# USB3_Replication.net
KiCad netlist of a schematic drawn in Altium Designer
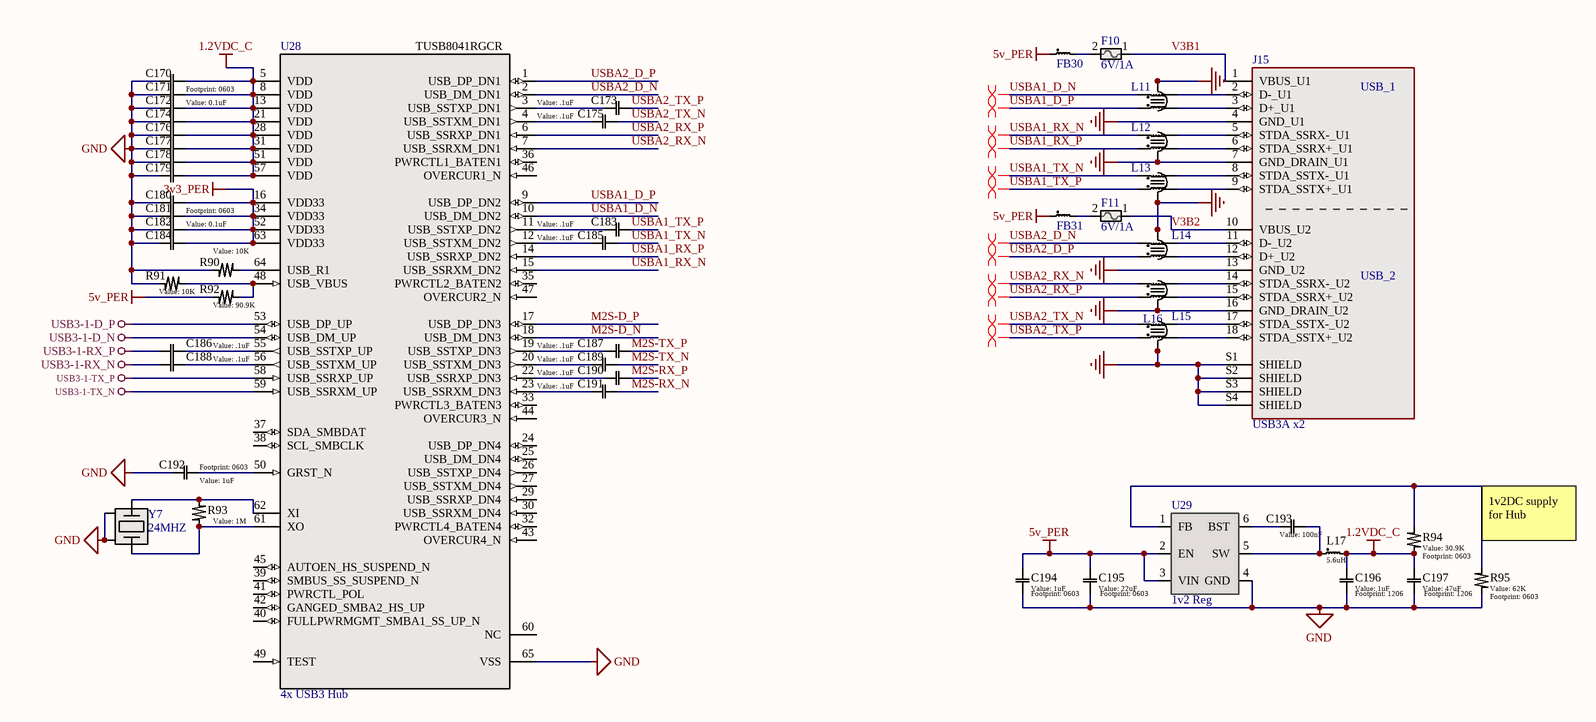
[diagram p0: USB3_Replication.SchDoc]

(export (version "E")
  (design (tool "Eeschema 10.0.6"))
  (components
    (comp (ref "C170")
      (value "0.1uF")
      (footprint "0603")
      (fields
        (field (name "VOLTAGE") "10V")
        (field (name "TOLERANCE") "10%")
        (field (name "Comment") "Generic Capacitor")
      )
      (libsource (lib "Capacitors") (part "Generic Capacitor"))
    )
    (comp (ref "C171")
      (value "Generic Capacitor")
      (footprint "0603")
      (fields (field (name "VOLTAGE") "10V") (field (name "TOLERANCE") "10%"))
      (libsource (lib "Capacitors") (part "Generic Capacitor"))
    )
    (comp (ref "C172")
      (value "Generic Capacitor")
      (footprint "0603")
      (fields (field (name "VOLTAGE") "10V") (field (name "TOLERANCE") "10%"))
      (libsource (lib "Capacitors") (part "Generic Capacitor"))
    )
    (comp (ref "C173")
      (value ".1uF")
      (footprint "0603")
      (fields
        (field (name "VOLTAGE") ">10V")
        (field (name "TOLERANCE") "10%")
        (field (name "Comment") "Generic Capacitor")
      )
      (libsource (lib "Capacitors") (part "Generic Capacitor"))
    )
    (comp (ref "C174")
      (value "Generic Capacitor")
      (footprint "0603")
      (fields (field (name "VOLTAGE") "10V") (field (name "TOLERANCE") "10%"))
      (libsource (lib "Capacitors") (part "Generic Capacitor"))
    )
    (comp (ref "C175")
      (value ".1uF")
      (footprint "0603")
      (fields
        (field (name "VOLTAGE") ">10V")
        (field (name "TOLERANCE") "10%")
        (field (name "Comment") "Generic Capacitor")
      )
      (libsource (lib "Capacitors") (part "Generic Capacitor"))
    )
    (comp (ref "C176")
      (value "Generic Capacitor")
      (footprint "0603")
      (fields (field (name "VOLTAGE") "10V") (field (name "TOLERANCE") "10%"))
      (libsource (lib "Capacitors") (part "Generic Capacitor"))
    )
    (comp (ref "C177")
      (value "Generic Capacitor")
      (footprint "0603")
      (fields (field (name "VOLTAGE") "10V") (field (name "TOLERANCE") "10%"))
      (libsource (lib "Capacitors") (part "Generic Capacitor"))
    )
    (comp (ref "C178")
      (value "Generic Capacitor")
      (footprint "0603")
      (fields (field (name "VOLTAGE") "10V") (field (name "TOLERANCE") "10%"))
      (libsource (lib "Capacitors") (part "Generic Capacitor"))
    )
    (comp (ref "C179")
      (value "Generic Capacitor")
      (footprint "0603")
      (fields (field (name "VOLTAGE") "10V") (field (name "TOLERANCE") "10%"))
      (libsource (lib "Capacitors") (part "Generic Capacitor"))
    )
    (comp (ref "C180")
      (value "0.1uF")
      (footprint "0603")
      (fields
        (field (name "VOLTAGE") "10V")
        (field (name "TOLERANCE") "10%")
        (field (name "Comment") "Generic Capacitor")
      )
      (libsource (lib "Capacitors") (part "Generic Capacitor"))
    )
    (comp (ref "C181")
      (value "Generic Capacitor")
      (footprint "0603")
      (fields (field (name "VOLTAGE") "10V") (field (name "TOLERANCE") "10%"))
      (libsource (lib "Capacitors") (part "Generic Capacitor"))
    )
    (comp (ref "C182")
      (value "Generic Capacitor")
      (footprint "0603")
      (fields (field (name "VOLTAGE") "10V") (field (name "TOLERANCE") "10%"))
      (libsource (lib "Capacitors") (part "Generic Capacitor"))
    )
    (comp (ref "C183")
      (value ".1uF")
      (footprint "0603")
      (fields
        (field (name "VOLTAGE") ">10V")
        (field (name "TOLERANCE") "10%")
        (field (name "Comment") "Generic Capacitor")
      )
      (libsource (lib "Capacitors") (part "Generic Capacitor"))
    )
    (comp (ref "C184")
      (value "Generic Capacitor")
      (footprint "0603")
      (fields (field (name "VOLTAGE") "10V") (field (name "TOLERANCE") "10%"))
      (libsource (lib "Capacitors") (part "Generic Capacitor"))
    )
    (comp (ref "C185")
      (value ".1uF")
      (footprint "0603")
      (fields
        (field (name "VOLTAGE") ">10V")
        (field (name "TOLERANCE") "10%")
        (field (name "Comment") "Generic Capacitor")
      )
      (libsource (lib "Capacitors") (part "Generic Capacitor"))
    )
    (comp (ref "C186")
      (value ".1uF")
      (footprint "0603")
      (fields
        (field (name "VOLTAGE") ">10V")
        (field (name "TOLERANCE") "10%")
        (field (name "Comment") "Generic Capacitor")
      )
      (libsource (lib "Capacitors") (part "Generic Capacitor"))
    )
    (comp (ref "C187")
      (value ".1uF")
      (footprint "0603")
      (fields
        (field (name "VOLTAGE") ">10V")
        (field (name "TOLERANCE") "10%")
        (field (name "Comment") "Generic Capacitor")
      )
      (libsource (lib "Capacitors") (part "Generic Capacitor"))
    )
    (comp (ref "C188")
      (value ".1uF")
      (footprint "0603")
      (fields
        (field (name "VOLTAGE") ">10V")
        (field (name "TOLERANCE") "10%")
        (field (name "Comment") "Generic Capacitor")
      )
      (libsource (lib "Capacitors") (part "Generic Capacitor"))
    )
    (comp (ref "C189")
      (value ".1uF")
      (footprint "0603")
      (fields
        (field (name "VOLTAGE") ">10V")
        (field (name "TOLERANCE") "10%")
        (field (name "Comment") "Generic Capacitor")
      )
      (libsource (lib "Capacitors") (part "Generic Capacitor"))
    )
    (comp (ref "C190")
      (value ".1uF")
      (footprint "0603")
      (fields
        (field (name "VOLTAGE") ">10V")
        (field (name "TOLERANCE") "10%")
        (field (name "Comment") "Generic Capacitor")
      )
      (libsource (lib "Capacitors") (part "Generic Capacitor"))
    )
    (comp (ref "C191")
      (value ".1uF")
      (footprint "0603")
      (fields
        (field (name "VOLTAGE") ">10V")
        (field (name "TOLERANCE") "10%")
        (field (name "Comment") "Generic Capacitor")
      )
      (libsource (lib "Capacitors") (part "Generic Capacitor"))
    )
    (comp (ref "C192")
      (value "1uF")
      (footprint "0603")
      (fields
        (field (name "VOLTAGE") ">10V")
        (field (name "TOLERANCE") "10%")
        (field (name "Comment") "Generic Capacitor")
      )
      (libsource (lib "Capacitors") (part "Generic Capacitor"))
    )
    (comp (ref "C193")
      (value "100nF")
      (footprint "0603")
      (fields
        (field (name "VOLTAGE") ">10V")
        (field (name "TOLERANCE") "10%")
        (field (name "Comment") "Generic Capacitor")
      )
      (libsource (lib "Capacitors") (part "Generic Capacitor"))
    )
    (comp (ref "C194")
      (value "1uF")
      (footprint "0603")
      (fields
        (field (name "VOLTAGE") ">10V")
        (field (name "TOLERANCE") "10%")
        (field (name "Comment") "Generic Capacitor")
      )
      (libsource (lib "Capacitors") (part "Generic Capacitor"))
    )
    (comp (ref "C195")
      (value "22uF")
      (footprint "0603")
      (fields
        (field (name "VOLTAGE") ">10V")
        (field (name "TOLERANCE") "10%")
        (field (name "Comment") "Generic Capacitor")
      )
      (libsource (lib "Capacitors") (part "Generic Capacitor"))
    )
    (comp (ref "C196")
      (value "1uF")
      (footprint "1206")
      (fields
        (field (name "VOLTAGE") ">10V")
        (field (name "TOLERANCE") "10%")
        (field (name "Comment") "Generic Capacitor")
      )
      (libsource (lib "Capacitors") (part "Generic Capacitor"))
    )
    (comp (ref "C197")
      (value "47uF")
      (footprint "1206")
      (fields
        (field (name "VOLTAGE") ">10V")
        (field (name "TOLERANCE") "10%")
        (field (name "Comment") "Generic Capacitor")
      )
      (libsource (lib "Capacitors") (part "Generic Capacitor"))
    )
    (comp (ref "F10")
      (value "6V/1A")
      (footprint "0805")
      (description "Polymeric PTC Resettable Fuse 6V 1 A Ih Surface Mount 0805 (2012 Metric), Concave")
      (fields (field (name "MANUFACTURER") "Bel") (field (name "MANUFACTURER PART NUMBER") "0ZCK0100FF2E"))
      (libsource (lib "Regulators") (part "0ZCK0100FF2E"))
    )
    (comp (ref "F11")
      (value "6V/1A")
      (footprint "0805")
      (description "Polymeric PTC Resettable Fuse 6V 1 A Ih Surface Mount 0805 (2012 Metric), Concave")
      (fields (field (name "MANUFACTURER") "Bel") (field (name "MANUFACTURER PART NUMBER") "0ZCK0100FF2E"))
      (libsource (lib "Regulators") (part "0ZCK0100FF2E"))
    )
    (comp (ref "FB30")
      (value "0603 Ferrite")
      (footprint "0603")
      (description "120 Ohms @ 100 MHz 1 Signal Line Ferrite Bead 0603 (1608 Metric) 500mA 180mOhm")
      (fields
        (field (name "MANUFACTURER") "Pulse")
        (field (name "MANUFACTURER PART NUMBER") "PE-0603FB121ST")
      )
      (libsource (lib "Inductors") (part "PE-0603FB121ST"))
    )
    (comp (ref "FB31")
      (value "0603 Ferrite")
      (footprint "0603")
      (description "120 Ohms @ 100 MHz 1 Signal Line Ferrite Bead 0603 (1608 Metric) 500mA 180mOhm")
      (fields
        (field (name "MANUFACTURER") "Pulse")
        (field (name "MANUFACTURER PART NUMBER") "PE-0603FB121ST")
      )
      (libsource (lib "Inductors") (part "PE-0603FB121ST"))
    )
    (comp (ref "J15")
      (value "USB3A x2")
      (footprint "0484060003")
      (fields (field (name "MP") "0484060003") (field (name "MF") "Molex"))
      (libsource (lib "Connectors") (part "0484060003"))
    )
    (comp (ref "L11")
      (value "2CH CMC")
      (footprint "SMD-6-2CH")
      (description "35Ω@100MHz -40℃~+85℃ 4Ω 5V 2 100mA SMD Common Mode Filters ROHS")
      (libsource (lib "") (part "ICMEF112P350MFR_1"))
    )
    (comp (ref "L12")
      (value "2CH CMC")
      (footprint "SMD-6-2CH")
      (description "35Ω@100MHz -40℃~+85℃ 4Ω 5V 2 100mA SMD Common Mode Filters ROHS")
      (libsource (lib "Inductors") (part "ICMEF112P350MFR"))
    )
    (comp (ref "L13")
      (value "2CH CMC")
      (footprint "SMD-6-2CH")
      (description "35Ω@100MHz -40℃~+85℃ 4Ω 5V 2 100mA SMD Common Mode Filters ROHS")
      (libsource (lib "Inductors") (part "ICMEF112P350MFR"))
    )
    (comp (ref "L14")
      (value "2CH CMC")
      (footprint "SMD-6-2CH")
      (description "35Ω@100MHz -40℃~+85℃ 4Ω 5V 2 100mA SMD Common Mode Filters ROHS")
      (libsource (lib "") (part "ICMEF112P350MFR_1"))
    )
    (comp (ref "L15")
      (value "2CH CMC")
      (footprint "SMD-6-2CH")
      (description "35Ω@100MHz -40℃~+85℃ 4Ω 5V 2 100mA SMD Common Mode Filters ROHS")
      (libsource (lib "Inductors") (part "ICMEF112P350MFR"))
    )
    (comp (ref "L16")
      (value "2CH CMC")
      (footprint "SMD-6-2CH")
      (description "35Ω@100MHz -40℃~+85℃ 4Ω 5V 2 100mA SMD Common Mode Filters ROHS")
      (libsource (lib "Inductors") (part "ICMEF112P350MFR"))
    )
    (comp (ref "L17")
      (value "5.6uH")
      (footprint "TMPC0402HP")
      (description "2A 5.6uH ±20% SMD Power Inductor")
      (libsource (lib "Inductors") (part "TMPC0402HP-5R6MG-Z02"))
    )
    (comp (ref "R90")
      (value "10K")
      (footprint "0603")
      (fields
        (field (name "TOLERANCE") "1%")
        (field (name "POWER") "1/10W")
        (field (name "Comment") "Generic Resistor")
      )
      (libsource (lib "Resistors") (part "Generic Resistor"))
    )
    (comp (ref "R91")
      (value "10K")
      (footprint "0603")
      (fields
        (field (name "TOLERANCE") "1%")
        (field (name "POWER") "1/10W")
        (field (name "Comment") "Generic Resistor")
      )
      (libsource (lib "Resistors") (part "Generic Resistor"))
    )
    (comp (ref "R92")
      (value "90.9K")
      (footprint "0603")
      (fields
        (field (name "TOLERANCE") "1%")
        (field (name "POWER") "1/10W")
        (field (name "Comment") "Generic Resistor")
      )
      (libsource (lib "Resistors") (part "Generic Resistor"))
    )
    (comp (ref "R93")
      (value "1M")
      (footprint "0603")
      (fields
        (field (name "TOLERANCE") "1%")
        (field (name "POWER") "1/10W")
        (field (name "Comment") "Generic Resistor")
      )
      (libsource (lib "Resistors") (part "Generic Resistor"))
    )
    (comp (ref "R94")
      (value "30.9K")
      (footprint "0603")
      (fields
        (field (name "TOLERANCE") "1%")
        (field (name "POWER") "1/10W")
        (field (name "Comment") "Generic Resistor")
      )
      (libsource (lib "Resistors") (part "Generic Resistor"))
    )
    (comp (ref "R95")
      (value "62K")
      (footprint "0603")
      (fields
        (field (name "TOLERANCE") "1%")
        (field (name "POWER") "1/10W")
        (field (name "Comment") "Generic Resistor")
      )
      (libsource (lib "Resistors") (part "Generic Resistor"))
    )
    (comp (ref "U28")
      (value "4x USB3 Hub")
      (footprint "QFN-64")
      (description "USB Hub Controller USB 3.0 USB, GPIO, I2C, SMBus Interface 64-VQFN (9x9)")
      (fields
        (field (name "PARTNUMBER") "TUSB8041RGCR")
        (field (name "ALTERNATE_PARTNUMBER") "TUSB8041RGCT")
        (field (name "MANUFACTURER") "Texas Instruments")
      )
      (libsource (lib "Hub ICs") (part "TUSB8041RGCR"))
    )
    (comp (ref "U29")
      (value "1v2 Reg")
      (footprint "TSOT-23-6")
      (description "Step-down type Adjustable 2A 1.2V~12V 3.8V~32V TSOT-23-6 DC-DC Converter")
      (libsource (lib "Regulators") (part "AP63201WU-7"))
    )
    (comp (ref "Y7")
      (value "24MHZ")
      (footprint "SMD2520-4P")
      (description "24MHz 20pF ±10ppm ±30ppm SMD-2520-4P Crystals ROHS")
      (libsource (lib "Clock ICs") (part "CM4024M00020001"))
    )
  )
  (nets
    (net (code "1") (name "/M2S-D_N") (class "Default")
      (node (ref "U28") (pin "18") (pinfunction "USB_DM_DN3_18") (pintype "bidirectional"))
    )
    (net (code "2") (name "/M2S-D_P") (class "Default")
      (node (ref "U28") (pin "17") (pinfunction "USB_DP_DN3_17") (pintype "bidirectional"))
    )
    (net (code "3") (name "/M2S-RX_N") (class "Default")
      (node (ref "C191") (pin "2") (pinfunction "2_2") (pintype "passive"))
    )
    (net (code "4") (name "/M2S-RX_P") (class "Default")
      (node (ref "C190") (pin "2") (pinfunction "2_2") (pintype "passive"))
    )
    (net (code "5") (name "/M2S-TX_N") (class "Default")
      (node (ref "C189") (pin "2") (pinfunction "2_2") (pintype "passive"))
    )
    (net (code "6") (name "/M2S-TX_P") (class "Default")
      (node (ref "C187") (pin "2") (pinfunction "2_2") (pintype "passive"))
    )
    (net (code "7") (name "/USBA1_D_N") (class "Default")
      (node (ref "L11") (pin "2") (pinfunction "2_2") (pintype "passive"))
      (node (ref "U28") (pin "10") (pinfunction "USB_DM_DN2_10") (pintype "bidirectional"))
    )
    (net (code "8") (name "/USBA1_D_P") (class "Default")
      (node (ref "L11") (pin "1") (pinfunction "1_1") (pintype "passive"))
      (node (ref "U28") (pin "9") (pinfunction "USB_DP_DN2_9") (pintype "bidirectional"))
    )
    (net (code "9") (name "/USBA1_RX_N") (class "Default")
      (node (ref "L12") (pin "1") (pinfunction "1_1") (pintype "passive"))
      (node (ref "U28") (pin "15") (pinfunction "USB_SSRXM_DN2_15") (pintype "input"))
    )
    (net (code "10") (name "/USBA1_RX_P") (class "Default")
      (node (ref "L12") (pin "2") (pinfunction "2_2") (pintype "passive"))
      (node (ref "U28") (pin "14") (pinfunction "USB_SSRXP_DN2_14") (pintype "input"))
    )
    (net (code "11") (name "/USBA1_TX_N") (class "Default")
      (node (ref "C185") (pin "2") (pinfunction "2_2") (pintype "passive"))
      (node (ref "L13") (pin "1") (pinfunction "1_1") (pintype "passive"))
    )
    (net (code "12") (name "/USBA1_TX_P") (class "Default")
      (node (ref "C183") (pin "2") (pinfunction "2_2") (pintype "passive"))
      (node (ref "L13") (pin "2") (pinfunction "2_2") (pintype "passive"))
    )
    (net (code "13") (name "/USBA2_D_N") (class "Default")
      (node (ref "L14") (pin "2") (pinfunction "2_2") (pintype "passive"))
      (node (ref "U28") (pin "2") (pinfunction "USB_DM_DN1_2") (pintype "bidirectional"))
    )
    (net (code "14") (name "/USBA2_D_P") (class "Default")
      (node (ref "L14") (pin "1") (pinfunction "1_1") (pintype "passive"))
      (node (ref "U28") (pin "1") (pinfunction "USB_DP_DN1_1") (pintype "bidirectional"))
    )
    (net (code "15") (name "/USBA2_RX_N") (class "Default")
      (node (ref "L16") (pin "1") (pinfunction "1_1") (pintype "passive"))
      (node (ref "U28") (pin "7") (pinfunction "USB_SSRXM_DN1_7") (pintype "input"))
    )
    (net (code "16") (name "/USBA2_RX_P") (class "Default")
      (node (ref "L16") (pin "2") (pinfunction "2_2") (pintype "passive"))
      (node (ref "U28") (pin "6") (pinfunction "USB_SSRXP_DN1_6") (pintype "input"))
    )
    (net (code "17") (name "/USBA2_TX_N") (class "Default")
      (node (ref "C175") (pin "2") (pinfunction "2_2") (pintype "passive"))
      (node (ref "L15") (pin "1") (pinfunction "1_1") (pintype "passive"))
    )
    (net (code "18") (name "/USBA2_TX_P") (class "Default")
      (node (ref "C173") (pin "2") (pinfunction "2_2") (pintype "passive"))
      (node (ref "L15") (pin "2") (pinfunction "2_2") (pintype "passive"))
    )
    (net (code "19") (name "/V3B1") (class "Default")
      (node (ref "F10") (pin "1") (pinfunction "1_1") (pintype "passive"))
      (node (ref "J15") (pin "1") (pinfunction "VBUS_U1_1") (pintype "power_in"))
    )
    (net (code "20") (name "/V3B2") (class "Default")
      (node (ref "F11") (pin "1") (pinfunction "1_1") (pintype "passive"))
      (node (ref "J15") (pin "10") (pinfunction "VBUS_U2_10") (pintype "power_in"))
    )
    (net (code "21") (name "1.2VDC_C") (class "Default")
      (node (ref "C170") (pin "1") (pinfunction "1_1") (pintype "passive"))
      (node (ref "C171") (pin "1") (pinfunction "1_1") (pintype "passive"))
      (node (ref "C172") (pin "1") (pinfunction "1_1") (pintype "passive"))
      (node (ref "C174") (pin "1") (pinfunction "1_1") (pintype "passive"))
      (node (ref "C176") (pin "1") (pinfunction "1_1") (pintype "passive"))
      (node (ref "C177") (pin "1") (pinfunction "1_1") (pintype "passive"))
      (node (ref "C178") (pin "1") (pinfunction "1_1") (pintype "passive"))
      (node (ref "C179") (pin "1") (pinfunction "1_1") (pintype "passive"))
      (node (ref "C196") (pin "1") (pinfunction "1_1") (pintype "passive"))
      (node (ref "C197") (pin "1") (pinfunction "1_1") (pintype "passive"))
      (node (ref "L17") (pin "2") (pinfunction "2_2") (pintype "passive"))
      (node (ref "R94") (pin "1") (pinfunction "1_1") (pintype "passive"))
      (node (ref "U28") (pin "13") (pinfunction "VDD_13") (pintype "power_in"))
      (node (ref "U28") (pin "21") (pinfunction "VDD_21") (pintype "power_in"))
      (node (ref "U28") (pin "28") (pinfunction "VDD_28") (pintype "power_in"))
      (node (ref "U28") (pin "31") (pinfunction "VDD_31") (pintype "power_in"))
      (node (ref "U28") (pin "5") (pinfunction "VDD_5") (pintype "power_in"))
      (node (ref "U28") (pin "51") (pinfunction "VDD_51") (pintype "power_in"))
      (node (ref "U28") (pin "57") (pinfunction "VDD_57") (pintype "power_in"))
      (node (ref "U28") (pin "8") (pinfunction "VDD_8") (pintype "power_in"))
    )
    (net (code "22") (name "3v3_PER") (class "Default")
      (node (ref "C180") (pin "1") (pinfunction "1_1") (pintype "passive"))
      (node (ref "C181") (pin "1") (pinfunction "1_1") (pintype "passive"))
      (node (ref "C182") (pin "1") (pinfunction "1_1") (pintype "passive"))
      (node (ref "C184") (pin "1") (pinfunction "1_1") (pintype "passive"))
      (node (ref "U28") (pin "16") (pinfunction "VDD33_16") (pintype "power_in"))
      (node (ref "U28") (pin "34") (pinfunction "VDD33_34") (pintype "power_in"))
      (node (ref "U28") (pin "52") (pinfunction "VDD33_52") (pintype "power_in"))
      (node (ref "U28") (pin "63") (pinfunction "VDD33_63") (pintype "power_in"))
    )
    (net (code "23") (name "5v_PER") (class "Default")
      (node (ref "C194") (pin "1") (pinfunction "1_1") (pintype "passive"))
      (node (ref "C195") (pin "1") (pinfunction "1_1") (pintype "passive"))
      (node (ref "FB30") (pin "1") (pinfunction "1_1") (pintype "passive"))
      (node (ref "FB31") (pin "1") (pinfunction "1_1") (pintype "passive"))
      (node (ref "R92") (pin "1") (pinfunction "1_1") (pintype "passive"))
      (node (ref "U29") (pin "2") (pinfunction "EN_2") (pintype "passive"))
      (node (ref "U29") (pin "3") (pinfunction "VIN_3") (pintype "passive"))
    )
    (net (code "24") (name "GND") (class "Default")
      (node (ref "C170") (pin "2") (pinfunction "2_2") (pintype "passive"))
      (node (ref "C171") (pin "2") (pinfunction "2_2") (pintype "passive"))
      (node (ref "C172") (pin "2") (pinfunction "2_2") (pintype "passive"))
      (node (ref "C174") (pin "2") (pinfunction "2_2") (pintype "passive"))
      (node (ref "C176") (pin "2") (pinfunction "2_2") (pintype "passive"))
      (node (ref "C177") (pin "2") (pinfunction "2_2") (pintype "passive"))
      (node (ref "C178") (pin "2") (pinfunction "2_2") (pintype "passive"))
      (node (ref "C179") (pin "2") (pinfunction "2_2") (pintype "passive"))
      (node (ref "C180") (pin "2") (pinfunction "2_2") (pintype "passive"))
      (node (ref "C181") (pin "2") (pinfunction "2_2") (pintype "passive"))
      (node (ref "C182") (pin "2") (pinfunction "2_2") (pintype "passive"))
      (node (ref "C184") (pin "2") (pinfunction "2_2") (pintype "passive"))
      (node (ref "C192") (pin "1") (pinfunction "1_1") (pintype "passive"))
      (node (ref "C194") (pin "2") (pinfunction "2_2") (pintype "passive"))
      (node (ref "C195") (pin "2") (pinfunction "2_2") (pintype "passive"))
      (node (ref "C196") (pin "2") (pinfunction "2_2") (pintype "passive"))
      (node (ref "C197") (pin "2") (pinfunction "2_2") (pintype "passive"))
      (node (ref "J15") (pin "13") (pinfunction "GND_U2_13") (pintype "power_in"))
      (node (ref "J15") (pin "16") (pinfunction "GND_DRAIN_U2_16") (pintype "power_in"))
      (node (ref "J15") (pin "4") (pinfunction "GND_U1_4") (pintype "power_in"))
      (node (ref "J15") (pin "7") (pinfunction "GND_DRAIN_U1_7") (pintype "power_in"))
      (node (ref "J15") (pin "S1") (pinfunction "SHIELD_S1") (pintype "passive"))
      (node (ref "J15") (pin "S2") (pinfunction "SHIELD_S2") (pintype "passive"))
      (node (ref "J15") (pin "S3") (pinfunction "SHIELD_S3") (pintype "passive"))
      (node (ref "J15") (pin "S4") (pinfunction "SHIELD_S4") (pintype "passive"))
      (node (ref "L11") (pin "5") (pinfunction "5_5") (pintype "passive"))
      (node (ref "L11") (pin "6") (pinfunction "6_6") (pintype "passive"))
      (node (ref "L12") (pin "5") (pinfunction "5_5") (pintype "passive"))
      (node (ref "L12") (pin "6") (pinfunction "6_6") (pintype "passive"))
      (node (ref "L13") (pin "5") (pinfunction "5_5") (pintype "passive"))
      (node (ref "L13") (pin "6") (pinfunction "6_6") (pintype "passive"))
      (node (ref "L14") (pin "5") (pinfunction "5_5") (pintype "passive"))
      (node (ref "L14") (pin "6") (pinfunction "6_6") (pintype "passive"))
      (node (ref "L15") (pin "5") (pinfunction "5_5") (pintype "passive"))
      (node (ref "L15") (pin "6") (pinfunction "6_6") (pintype "passive"))
      (node (ref "L16") (pin "5") (pinfunction "5_5") (pintype "passive"))
      (node (ref "L16") (pin "6") (pinfunction "6_6") (pintype "passive"))
      (node (ref "R90") (pin "1") (pinfunction "1_1") (pintype "passive"))
      (node (ref "R91") (pin "2") (pinfunction "2_2") (pintype "passive"))
      (node (ref "R95") (pin "1") (pinfunction "1_1") (pintype "passive"))
      (node (ref "U28") (pin "65") (pinfunction "VSS_65") (pintype "power_in"))
      (node (ref "U29") (pin "4") (pinfunction "GND_4") (pintype "power_in"))
      (node (ref "Y7") (pin "2") (pinfunction "GND_2") (pintype "power_in"))
      (node (ref "Y7") (pin "4") (pinfunction "GND_4") (pintype "power_in"))
    )
    (net (code "25") (name "Net-(F10-Pad2)") (class "Default")
      (node (ref "F10") (pin "2") (pinfunction "2_2") (pintype "passive"))
      (node (ref "FB30") (pin "2") (pinfunction "2_2") (pintype "passive"))
    )
    (net (code "26") (name "Net-(F11-Pad2)") (class "Default")
      (node (ref "F11") (pin "2") (pinfunction "2_2") (pintype "passive"))
      (node (ref "FB31") (pin "2") (pinfunction "2_2") (pintype "passive"))
    )
    (net (code "27") (name "Net-(J15-D+_U1)") (class "Default")
      (node (ref "J15") (pin "3") (pinfunction "D+_U1_3") (pintype "bidirectional"))
      (node (ref "L11") (pin "4") (pinfunction "4_4") (pintype "passive"))
    )
    (net (code "28") (name "Net-(J15-D+_U2)") (class "Default")
      (node (ref "J15") (pin "12") (pinfunction "D+_U2_12") (pintype "bidirectional"))
      (node (ref "L14") (pin "4") (pinfunction "4_4") (pintype "passive"))
    )
    (net (code "29") (name "Net-(J15-D-_U1)") (class "Default")
      (node (ref "J15") (pin "2") (pinfunction "D-_U1_2") (pintype "bidirectional"))
      (node (ref "L11") (pin "3") (pinfunction "3_3") (pintype "passive"))
    )
    (net (code "30") (name "Net-(J15-D-_U2)") (class "Default")
      (node (ref "J15") (pin "11") (pinfunction "D-_U2_11") (pintype "bidirectional"))
      (node (ref "L14") (pin "3") (pinfunction "3_3") (pintype "passive"))
    )
    (net (code "31") (name "Net-(J15-STDA_SSRX+_U1)") (class "Default")
      (node (ref "J15") (pin "6") (pinfunction "STDA_SSRX+_U1_6") (pintype "bidirectional"))
      (node (ref "L12") (pin "3") (pinfunction "3_3") (pintype "passive"))
    )
    (net (code "32") (name "Net-(J15-STDA_SSRX+_U2)") (class "Default")
      (node (ref "J15") (pin "15") (pinfunction "STDA_SSRX+_U2_15") (pintype "bidirectional"))
      (node (ref "L16") (pin "3") (pinfunction "3_3") (pintype "passive"))
    )
    (net (code "33") (name "Net-(J15-STDA_SSRX-_U1)") (class "Default")
      (node (ref "J15") (pin "5") (pinfunction "STDA_SSRX-_U1_5") (pintype "bidirectional"))
      (node (ref "L12") (pin "4") (pinfunction "4_4") (pintype "passive"))
    )
    (net (code "34") (name "Net-(J15-STDA_SSRX-_U2)") (class "Default")
      (node (ref "J15") (pin "14") (pinfunction "STDA_SSRX-_U2_14") (pintype "bidirectional"))
      (node (ref "L16") (pin "4") (pinfunction "4_4") (pintype "passive"))
    )
    (net (code "35") (name "Net-(J15-STDA_SSTX+_U1)") (class "Default")
      (node (ref "J15") (pin "9") (pinfunction "STDA_SSTX+_U1_9") (pintype "bidirectional"))
      (node (ref "L13") (pin "3") (pinfunction "3_3") (pintype "passive"))
    )
    (net (code "36") (name "Net-(J15-STDA_SSTX+_U2)") (class "Default")
      (node (ref "J15") (pin "18") (pinfunction "STDA_SSTX+_U2_18") (pintype "bidirectional"))
      (node (ref "L15") (pin "3") (pinfunction "3_3") (pintype "passive"))
    )
    (net (code "37") (name "Net-(J15-STDA_SSTX-_U1)") (class "Default")
      (node (ref "J15") (pin "8") (pinfunction "STDA_SSTX-_U1_8") (pintype "bidirectional"))
      (node (ref "L13") (pin "4") (pinfunction "4_4") (pintype "passive"))
    )
    (net (code "38") (name "Net-(J15-STDA_SSTX-_U2)") (class "Default")
      (node (ref "J15") (pin "17") (pinfunction "STDA_SSTX-_U2_17") (pintype "bidirectional"))
      (node (ref "L15") (pin "4") (pinfunction "4_4") (pintype "passive"))
    )
    (net (code "39") (name "Net-(U28-GRST_N)") (class "Default")
      (node (ref "C192") (pin "2") (pinfunction "2_2") (pintype "passive"))
      (node (ref "U28") (pin "50") (pinfunction "GRST_N_50") (pintype "input"))
    )
    (net (code "40") (name "Net-(U28-USB_R1)") (class "Default")
      (node (ref "R90") (pin "2") (pinfunction "2_2") (pintype "passive"))
      (node (ref "U28") (pin "64") (pinfunction "USB_R1_64") (pintype "passive"))
    )
    (net (code "41") (name "Net-(U28-USB_SSRXM_DN3)") (class "Default")
      (node (ref "C191") (pin "1") (pinfunction "1_1") (pintype "passive"))
      (node (ref "U28") (pin "23") (pinfunction "USB_SSRXM_DN3_23") (pintype "input"))
    )
    (net (code "42") (name "Net-(U28-USB_SSRXP_DN3)") (class "Default")
      (node (ref "C190") (pin "1") (pinfunction "1_1") (pintype "passive"))
      (node (ref "U28") (pin "22") (pinfunction "USB_SSRXP_DN3_22") (pintype "input"))
    )
    (net (code "43") (name "Net-(U28-USB_SSTXM_DN1)") (class "Default")
      (node (ref "C175") (pin "1") (pinfunction "1_1") (pintype "passive"))
      (node (ref "U28") (pin "4") (pinfunction "USB_SSTXM_DN1_4") (pintype "output"))
    )
    (net (code "44") (name "Net-(U28-USB_SSTXM_DN2)") (class "Default")
      (node (ref "C185") (pin "1") (pinfunction "1_1") (pintype "passive"))
      (node (ref "U28") (pin "12") (pinfunction "USB_SSTXM_DN2_12") (pintype "output"))
    )
    (net (code "45") (name "Net-(U28-USB_SSTXM_DN3)") (class "Default")
      (node (ref "C189") (pin "1") (pinfunction "1_1") (pintype "passive"))
      (node (ref "U28") (pin "20") (pinfunction "USB_SSTXM_DN3_20") (pintype "output"))
    )
    (net (code "46") (name "Net-(U28-USB_SSTXM_UP)") (class "Default")
      (node (ref "C188") (pin "1") (pinfunction "1_1") (pintype "passive"))
      (node (ref "U28") (pin "56") (pinfunction "USB_SSTXM_UP_56") (pintype "output"))
    )
    (net (code "47") (name "Net-(U28-USB_SSTXP_DN1)") (class "Default")
      (node (ref "C173") (pin "1") (pinfunction "1_1") (pintype "passive"))
      (node (ref "U28") (pin "3") (pinfunction "USB_SSTXP_DN1_3") (pintype "output"))
    )
    (net (code "48") (name "Net-(U28-USB_SSTXP_DN2)") (class "Default")
      (node (ref "C183") (pin "1") (pinfunction "1_1") (pintype "passive"))
      (node (ref "U28") (pin "11") (pinfunction "USB_SSTXP_DN2_11") (pintype "output"))
    )
    (net (code "49") (name "Net-(U28-USB_SSTXP_DN3)") (class "Default")
      (node (ref "C187") (pin "1") (pinfunction "1_1") (pintype "passive"))
      (node (ref "U28") (pin "19") (pinfunction "USB_SSTXP_DN3_19") (pintype "output"))
    )
    (net (code "50") (name "Net-(U28-USB_SSTXP_UP)") (class "Default")
      (node (ref "C186") (pin "1") (pinfunction "1_1") (pintype "passive"))
      (node (ref "U28") (pin "55") (pinfunction "USB_SSTXP_UP_55") (pintype "output"))
    )
    (net (code "51") (name "Net-(U28-USB_VBUS)") (class "Default")
      (node (ref "R91") (pin "1") (pinfunction "1_1") (pintype "passive"))
      (node (ref "R92") (pin "2") (pinfunction "2_2") (pintype "passive"))
      (node (ref "U28") (pin "48") (pinfunction "USB_VBUS_48") (pintype "input"))
    )
    (net (code "52") (name "Net-(U28-XI)") (class "Default")
      (node (ref "R93") (pin "1") (pinfunction "1_1") (pintype "passive"))
      (node (ref "U28") (pin "62") (pinfunction "XI_62") (pintype "passive"))
      (node (ref "Y7") (pin "1") (pintype "passive"))
    )
    (net (code "53") (name "Net-(U28-XO)") (class "Default")
      (node (ref "R93") (pin "2") (pinfunction "2_2") (pintype "passive"))
      (node (ref "U28") (pin "61") (pinfunction "XO_61") (pintype "passive"))
      (node (ref "Y7") (pin "3") (pintype "passive"))
    )
    (net (code "54") (name "Net-(U29-BST)") (class "Default")
      (node (ref "C193") (pin "1") (pinfunction "1_1") (pintype "passive"))
      (node (ref "U29") (pin "6") (pinfunction "BST_6") (pintype "passive"))
    )
    (net (code "55") (name "Net-(U29-FB)") (class "Default")
      (node (ref "R94") (pin "2") (pinfunction "2_2") (pintype "passive"))
      (node (ref "R95") (pin "2") (pinfunction "2_2") (pintype "passive"))
      (node (ref "U29") (pin "1") (pinfunction "FB_1") (pintype "passive"))
    )
    (net (code "56") (name "Net-(U29-SW)") (class "Default")
      (node (ref "C193") (pin "2") (pinfunction "2_2") (pintype "passive"))
      (node (ref "L17") (pin "1") (pinfunction "1_1") (pintype "passive"))
      (node (ref "U29") (pin "5") (pinfunction "SW_5") (pintype "passive"))
    )
    (net (code "57") (name "USB3-1-D_N") (class "Default")
      (node (ref "U28") (pin "54") (pinfunction "USB_DM_UP_54") (pintype "bidirectional"))
    )
    (net (code "58") (name "USB3-1-D_P") (class "Default")
      (node (ref "U28") (pin "53") (pinfunction "USB_DP_UP_53") (pintype "bidirectional"))
    )
    (net (code "59") (name "USB3-1-RX_N") (class "Default")
      (node (ref "C188") (pin "2") (pinfunction "2_2") (pintype "passive"))
    )
    (net (code "60") (name "USB3-1-RX_P") (class "Default")
      (node (ref "C186") (pin "2") (pinfunction "2_2") (pintype "passive"))
    )
    (net (code "61") (name "USB3-1-TX_N") (class "Default")
      (node (ref "U28") (pin "59") (pinfunction "USB_SSRXM_UP_59") (pintype "input"))
    )
    (net (code "62") (name "USB3-1-TX_P") (class "Default")
      (node (ref "U28") (pin "58") (pinfunction "USB_SSRXP_UP_58") (pintype "input"))
    )
    (net (code "63") (name "unconnected-(U28-AUTOEN_HS_SUSPEND_N-Pad45)") (class "Default")
      (node (ref "U28") (pin "45") (pinfunction "AUTOEN_HS_SUSPEND_N_45") (pintype "bidirectional"))
    )
    (net (code "64") (name "unconnected-(U28-FULLPWRMGMT_SMBA1_SS_UP_N-Pad40)") (class "Default")
      (node (ref "U28") (pin "40") (pinfunction "FULLPWRMGMT_SMBA1_SS_UP_N_40") (pintype "bidirectional"))
    )
    (net (code "65") (name "unconnected-(U28-GANGED_SMBA2_HS_UP-Pad42)") (class "Default")
      (node (ref "U28") (pin "42") (pinfunction "GANGED_SMBA2_HS_UP_42") (pintype "bidirectional"))
    )
    (net (code "66") (name "unconnected-(U28-NC-Pad60)") (class "Default")
      (node (ref "U28") (pin "60") (pinfunction "NC_60") (pintype "power_in"))
    )
    (net (code "67") (name "unconnected-(U28-OVERCUR1_N-Pad46)") (class "Default")
      (node (ref "U28") (pin "46") (pinfunction "OVERCUR1_N_46") (pintype "input"))
    )
    (net (code "68") (name "unconnected-(U28-OVERCUR2_N-Pad47)") (class "Default")
      (node (ref "U28") (pin "47") (pinfunction "OVERCUR2_N_47") (pintype "input"))
    )
    (net (code "69") (name "unconnected-(U28-OVERCUR3_N-Pad44)") (class "Default")
      (node (ref "U28") (pin "44") (pinfunction "OVERCUR3_N_44") (pintype "input"))
    )
    (net (code "70") (name "unconnected-(U28-OVERCUR4_N-Pad43)") (class "Default")
      (node (ref "U28") (pin "43") (pinfunction "OVERCUR4_N_43") (pintype "input"))
    )
    (net (code "71") (name "unconnected-(U28-PWRCTL1_BATEN1-Pad36)") (class "Default")
      (node (ref "U28") (pin "36") (pinfunction "PWRCTL1_BATEN1_36") (pintype "bidirectional"))
    )
    (net (code "72") (name "unconnected-(U28-PWRCTL2_BATEN2-Pad35)") (class "Default")
      (node (ref "U28") (pin "35") (pinfunction "PWRCTL2_BATEN2_35") (pintype "bidirectional"))
    )
    (net (code "73") (name "unconnected-(U28-PWRCTL3_BATEN3-Pad33)") (class "Default")
      (node (ref "U28") (pin "33") (pinfunction "PWRCTL3_BATEN3_33") (pintype "bidirectional"))
    )
    (net (code "74") (name "unconnected-(U28-PWRCTL4_BATEN4-Pad32)") (class "Default")
      (node (ref "U28") (pin "32") (pinfunction "PWRCTL4_BATEN4_32") (pintype "bidirectional"))
    )
    (net (code "75") (name "unconnected-(U28-PWRCTL_POL-Pad41)") (class "Default")
      (node (ref "U28") (pin "41") (pinfunction "PWRCTL_POL_41") (pintype "bidirectional"))
    )
    (net (code "76") (name "unconnected-(U28-SCL_SMBCLK-Pad38)") (class "Default")
      (node (ref "U28") (pin "38") (pinfunction "SCL_SMBCLK_38") (pintype "bidirectional"))
    )
    (net (code "77") (name "unconnected-(U28-SDA_SMBDAT-Pad37)") (class "Default")
      (node (ref "U28") (pin "37") (pinfunction "SDA_SMBDAT_37") (pintype "bidirectional"))
    )
    (net (code "78") (name "unconnected-(U28-SMBUS_SS_SUSPEND_N-Pad39)") (class "Default")
      (node (ref "U28") (pin "39") (pinfunction "SMBUS_SS_SUSPEND_N_39") (pintype "bidirectional"))
    )
    (net (code "79") (name "unconnected-(U28-TEST-Pad49)") (class "Default")
      (node (ref "U28") (pin "49") (pinfunction "TEST_49") (pintype "input"))
    )
    (net (code "80") (name "unconnected-(U28-USB_DM_DN4-Pad25)") (class "Default")
      (node (ref "U28") (pin "25") (pinfunction "USB_DM_DN4_25") (pintype "bidirectional"))
    )
    (net (code "81") (name "unconnected-(U28-USB_DP_DN4-Pad24)") (class "Default")
      (node (ref "U28") (pin "24") (pinfunction "USB_DP_DN4_24") (pintype "bidirectional"))
    )
    (net (code "82") (name "unconnected-(U28-USB_SSRXM_DN4-Pad30)") (class "Default")
      (node (ref "U28") (pin "30") (pinfunction "USB_SSRXM_DN4_30") (pintype "input"))
    )
    (net (code "83") (name "unconnected-(U28-USB_SSRXP_DN4-Pad29)") (class "Default")
      (node (ref "U28") (pin "29") (pinfunction "USB_SSRXP_DN4_29") (pintype "input"))
    )
    (net (code "84") (name "unconnected-(U28-USB_SSTXM_DN4-Pad27)") (class "Default")
      (node (ref "U28") (pin "27") (pinfunction "USB_SSTXM_DN4_27") (pintype "output"))
    )
    (net (code "85") (name "unconnected-(U28-USB_SSTXP_DN4-Pad26)") (class "Default")
      (node (ref "U28") (pin "26") (pinfunction "USB_SSTXP_DN4_26") (pintype "output"))
    )
  )
)
